# ISO_PWR_UCC12040DVER.net
KiCad netlist of a schematic drawn in Altium Designer
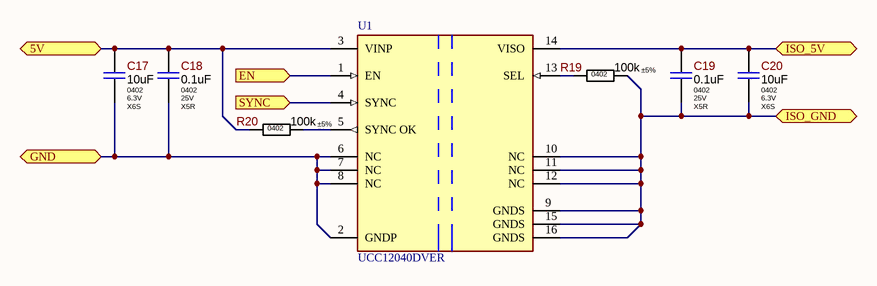
[diagram p0: ISO_PWR_UCC12040DVER.SchDoc]

(export (version "E")
  (design (tool "Eeschema 10.0.6"))
  (components
    (comp (ref "C17")
      (value "10uF")
      (footprint "C_CERAMIC_0402_MED")
      (description "10uF 6.3V X6S ±20% 0402 Ceramic Capacitor RoHS")
      (fields
        (field (name "PACKAGE") "0402")
        (field (name "VOLTAGE") "6.3V")
        (field (name "DIELECTRIC TYPE") "X6S")
        (field (name "PART NUMBER") "GRM155C80J106ME11D")
        (field (name "MANUFACTURER") "Murata Electronics")
      )
      (libsource (lib "EL.XXX.T01") (part "Capacitor-NonPolar"))
    )
    (comp (ref "C18")
      (value "0.1uF")
      (footprint "C_CERAMIC_0402_MED")
      (description "100nF 25V X5R ±10% 0402 Ceramic Capacitor RoHS")
      (fields
        (field (name "PACKAGE") "0402")
        (field (name "VOLTAGE") "25V")
        (field (name "DIELECTRIC TYPE") "X5R")
        (field (name "PART NUMBER") "CL05A104KA5NNNC")
        (field (name "MANUFACTURER") "Samsung Electro-Mechanics")
      )
      (libsource (lib "EL.XXX.T01") (part "Capacitor-NonPolar"))
    )
    (comp (ref "C19")
      (value "0.1uF")
      (footprint "C_CERAMIC_0402_MED")
      (description "100nF 25V X5R ±10% 0402 Ceramic Capacitor RoHS")
      (fields
        (field (name "PACKAGE") "0402")
        (field (name "VOLTAGE") "25V")
        (field (name "DIELECTRIC TYPE") "X5R")
        (field (name "PART NUMBER") "CL05A104KA5NNNC")
        (field (name "MANUFACTURER") "Samsung Electro-Mechanics")
      )
      (libsource (lib "EL.XXX.T01") (part "Capacitor-NonPolar"))
    )
    (comp (ref "C20")
      (value "10uF")
      (footprint "C_CERAMIC_0402_MED")
      (description "10uF 6.3V X6S ±20% 0402 Ceramic Capacitor RoHS")
      (fields
        (field (name "PACKAGE") "0402")
        (field (name "VOLTAGE") "6.3V")
        (field (name "DIELECTRIC TYPE") "X6S")
        (field (name "PART NUMBER") "GRM155C80J106ME11D")
        (field (name "MANUFACTURER") "Murata Electronics")
      )
      (libsource (lib "EL.XXX.T01") (part "Capacitor-NonPolar"))
    )
    (comp (ref "R19")
      (value "100k")
      (footprint "R_ANY_CHIP_0402_HI")
      (description "100 kOhms ±5% 1/16W 0402 Thick Film Resistor")
      (fields
        (field (name "TOLERANCE") "±5%")
        (field (name "PACKAGE") "0402")
        (field (name "PART NUMBER") "RC0402JR-07100KL")
        (field (name "MANUFACTURER") "Yageo")
      )
      (libsource (lib "EL.XXX.T01") (part "Resistor"))
    )
    (comp (ref "R20")
      (value "100k")
      (footprint "R_ANY_CHIP_0402_HI")
      (description "100 kOhms ±5% 1/16W 0402 Thick Film Resistor")
      (fields
        (field (name "TOLERANCE") "±5%")
        (field (name "PACKAGE") "0402")
        (field (name "PART NUMBER") "RC0402JR-07100KL")
        (field (name "MANUFACTURER") "Yageo")
      )
      (libsource (lib "EL.XXX.T01") (part "Resistor"))
    )
    (comp (ref "U1")
      (value "UCC12040DVER")
      (footprint "FP-DVE0016A-MFG")
      (description "DC DC CONVERTER 5V 500mW")
      (libsource (lib "EL.XXX.T01") (part "CMP-04910-000064-1"))
    )
  )
  (nets
    (net (code "1") (name "/5V") (class "Default")
      (node (ref "C17") (pin "1") (pinfunction "1_1") (pintype "passive"))
      (node (ref "C18") (pin "1") (pinfunction "1_1") (pintype "passive"))
      (node (ref "R20") (pin "1") (pintype "passive"))
      (node (ref "U1") (pin "3") (pinfunction "VINP_3") (pintype "power_in"))
    )
    (net (code "2") (name "/EN") (class "Default")
      (node (ref "U1") (pin "1") (pinfunction "EN_1") (pintype "input"))
    )
    (net (code "3") (name "/GND") (class "Default")
      (node (ref "C17") (pin "2") (pinfunction "2_2") (pintype "passive"))
      (node (ref "C18") (pin "2") (pinfunction "2_2") (pintype "passive"))
      (node (ref "U1") (pin "2") (pinfunction "GNDP_2") (pintype "power_in"))
      (node (ref "U1") (pin "6") (pinfunction "NC_6") (pintype "passive"))
      (node (ref "U1") (pin "7") (pinfunction "NC_7") (pintype "passive"))
      (node (ref "U1") (pin "8") (pinfunction "NC_8") (pintype "passive"))
    )
    (net (code "4") (name "/ISO_5V") (class "Default")
      (node (ref "C19") (pin "1") (pinfunction "1_1") (pintype "passive"))
      (node (ref "C20") (pin "1") (pinfunction "1_1") (pintype "passive"))
      (node (ref "U1") (pin "14") (pinfunction "VISO_14") (pintype "power_in"))
    )
    (net (code "5") (name "/ISO_GND") (class "Default")
      (node (ref "C19") (pin "2") (pinfunction "2_2") (pintype "passive"))
      (node (ref "C20") (pin "2") (pinfunction "2_2") (pintype "passive"))
      (node (ref "R19") (pin "2") (pintype "passive"))
      (node (ref "U1") (pin "10") (pinfunction "NC_10") (pintype "passive"))
      (node (ref "U1") (pin "11") (pinfunction "NC_11") (pintype "passive"))
      (node (ref "U1") (pin "12") (pinfunction "NC_12") (pintype "passive"))
      (node (ref "U1") (pin "15") (pinfunction "GNDS_15") (pintype "power_in"))
      (node (ref "U1") (pin "16") (pinfunction "GNDS_16") (pintype "power_in"))
      (node (ref "U1") (pin "9") (pinfunction "GNDS_9") (pintype "power_in"))
    )
    (net (code "6") (name "/SYNC") (class "Default")
      (node (ref "U1") (pin "4") (pinfunction "SYNC_4") (pintype "input"))
    )
    (net (code "7") (name "Net-(U1-SEL)") (class "Default")
      (node (ref "R19") (pin "1") (pintype "passive"))
      (node (ref "U1") (pin "13") (pinfunction "SEL_13") (pintype "input"))
    )
    (net (code "8") (name "Net-(U1-SYNC_OK)") (class "Default")
      (node (ref "R20") (pin "2") (pintype "passive"))
      (node (ref "U1") (pin "5") (pinfunction "SYNC_OK_5") (pintype "output"))
    )
  )
)
